# sondeSide.net
KiCad netlist of a schematic drawn in EAGLE
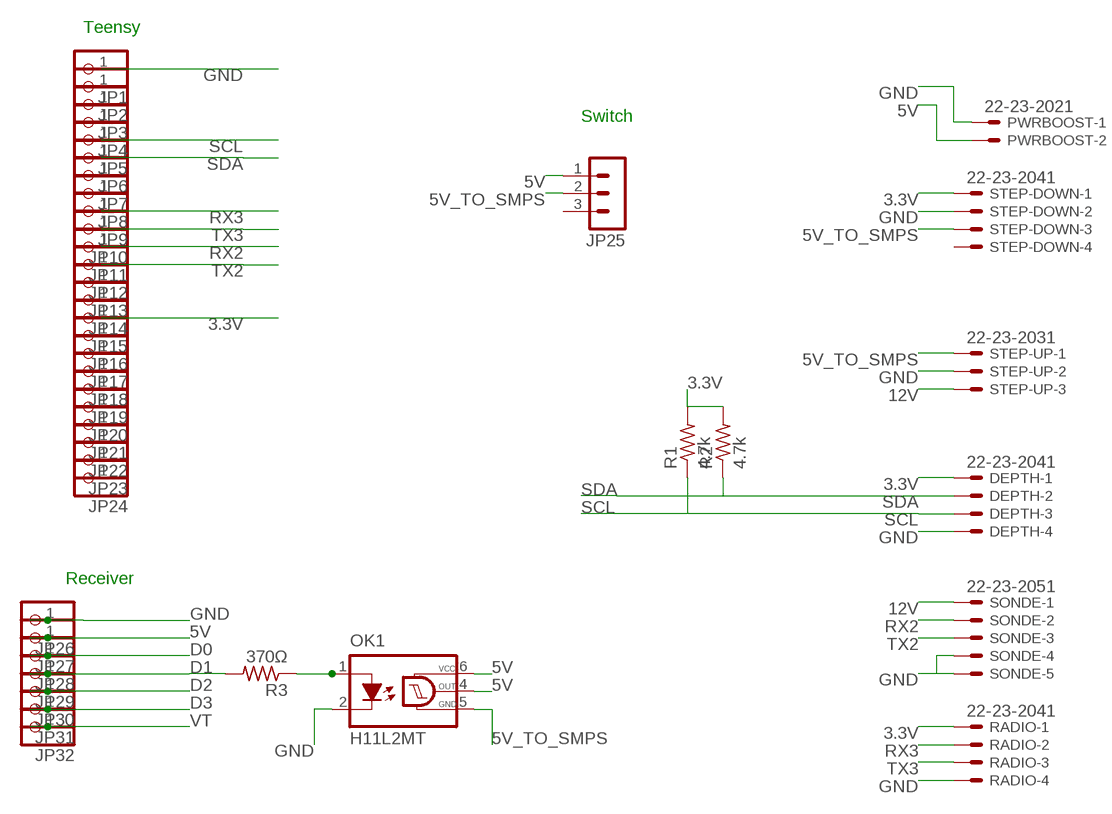
[diagram p0: schematic, sheet 1]

(export (version "E")
  (design (tool "Eeschema 10.0.6"))
  (components
    (comp (ref "DEPTH")
      (value "22-23-2041")
      (footprint "eagle-import:22-23-2041")
      (fields (field (name "MF") "MOLEX"))
      (libsource (lib "eagle-import") (part "22-23-2041"))
    )
    (comp (ref "JP1")
      (value "PINHD-1X1")
      (footprint "eagle-import:1X01")
      (libsource (lib "eagle-import") (part "PINHD-1X1"))
    )
    (comp (ref "JP2")
      (value "PINHD-1X1")
      (footprint "eagle-import:1X01")
      (libsource (lib "eagle-import") (part "PINHD-1X1"))
    )
    (comp (ref "JP3")
      (value "PINHD-1X1")
      (footprint "eagle-import:1X01")
      (libsource (lib "eagle-import") (part "PINHD-1X1"))
    )
    (comp (ref "JP4")
      (value "PINHD-1X1")
      (footprint "eagle-import:1X01")
      (libsource (lib "eagle-import") (part "PINHD-1X1"))
    )
    (comp (ref "JP5")
      (value "PINHD-1X1")
      (footprint "eagle-import:1X01")
      (libsource (lib "eagle-import") (part "PINHD-1X1"))
    )
    (comp (ref "JP6")
      (value "PINHD-1X1")
      (footprint "eagle-import:1X01")
      (libsource (lib "eagle-import") (part "PINHD-1X1"))
    )
    (comp (ref "JP7")
      (value "PINHD-1X1")
      (footprint "eagle-import:1X01")
      (libsource (lib "eagle-import") (part "PINHD-1X1"))
    )
    (comp (ref "JP8")
      (value "PINHD-1X1")
      (footprint "eagle-import:1X01")
      (libsource (lib "eagle-import") (part "PINHD-1X1"))
    )
    (comp (ref "JP9")
      (value "PINHD-1X1")
      (footprint "eagle-import:1X01")
      (libsource (lib "eagle-import") (part "PINHD-1X1"))
    )
    (comp (ref "JP10")
      (value "PINHD-1X1")
      (footprint "eagle-import:1X01")
      (libsource (lib "eagle-import") (part "PINHD-1X1"))
    )
    (comp (ref "JP11")
      (value "PINHD-1X1")
      (footprint "eagle-import:1X01")
      (libsource (lib "eagle-import") (part "PINHD-1X1"))
    )
    (comp (ref "JP12")
      (value "PINHD-1X1")
      (footprint "eagle-import:1X01")
      (libsource (lib "eagle-import") (part "PINHD-1X1"))
    )
    (comp (ref "JP13")
      (value "PINHD-1X1")
      (footprint "eagle-import:1X01")
      (libsource (lib "eagle-import") (part "PINHD-1X1"))
    )
    (comp (ref "JP14")
      (value "PINHD-1X1")
      (footprint "eagle-import:1X01")
      (libsource (lib "eagle-import") (part "PINHD-1X1"))
    )
    (comp (ref "JP15")
      (value "PINHD-1X1")
      (footprint "eagle-import:1X01")
      (libsource (lib "eagle-import") (part "PINHD-1X1"))
    )
    (comp (ref "JP16")
      (value "PINHD-1X1")
      (footprint "eagle-import:1X01")
      (libsource (lib "eagle-import") (part "PINHD-1X1"))
    )
    (comp (ref "JP17")
      (value "PINHD-1X1")
      (footprint "eagle-import:1X01")
      (libsource (lib "eagle-import") (part "PINHD-1X1"))
    )
    (comp (ref "JP18")
      (value "PINHD-1X1")
      (footprint "eagle-import:1X01")
      (libsource (lib "eagle-import") (part "PINHD-1X1"))
    )
    (comp (ref "JP19")
      (value "PINHD-1X1")
      (footprint "eagle-import:1X01")
      (libsource (lib "eagle-import") (part "PINHD-1X1"))
    )
    (comp (ref "JP20")
      (value "PINHD-1X1")
      (footprint "eagle-import:1X01")
      (libsource (lib "eagle-import") (part "PINHD-1X1"))
    )
    (comp (ref "JP21")
      (value "PINHD-1X1")
      (footprint "eagle-import:1X01")
      (libsource (lib "eagle-import") (part "PINHD-1X1"))
    )
    (comp (ref "JP22")
      (value "PINHD-1X1")
      (footprint "eagle-import:1X01")
      (libsource (lib "eagle-import") (part "PINHD-1X1"))
    )
    (comp (ref "JP23")
      (value "PINHD-1X1")
      (footprint "eagle-import:1X01")
      (libsource (lib "eagle-import") (part "PINHD-1X1"))
    )
    (comp (ref "JP24")
      (value "PINHD-1X1")
      (footprint "eagle-import:1X01")
      (libsource (lib "eagle-import") (part "PINHD-1X1"))
    )
    (comp (ref "JP25")
      (value "MA03-1")
      (footprint "eagle-import:MA03-1")
      (libsource (lib "eagle-import") (part "MA03-1"))
    )
    (comp (ref "JP26")
      (value "PINHD-1X1")
      (footprint "eagle-import:1X01")
      (libsource (lib "eagle-import") (part "PINHD-1X1"))
    )
    (comp (ref "JP27")
      (value "PINHD-1X1")
      (footprint "eagle-import:1X01")
      (libsource (lib "eagle-import") (part "PINHD-1X1"))
    )
    (comp (ref "JP28")
      (value "PINHD-1X1")
      (footprint "eagle-import:1X01")
      (libsource (lib "eagle-import") (part "PINHD-1X1"))
    )
    (comp (ref "JP29")
      (value "PINHD-1X1")
      (footprint "eagle-import:1X01")
      (libsource (lib "eagle-import") (part "PINHD-1X1"))
    )
    (comp (ref "JP30")
      (value "PINHD-1X1")
      (footprint "eagle-import:1X01")
      (libsource (lib "eagle-import") (part "PINHD-1X1"))
    )
    (comp (ref "JP31")
      (value "PINHD-1X1")
      (footprint "eagle-import:1X01")
      (libsource (lib "eagle-import") (part "PINHD-1X1"))
    )
    (comp (ref "JP32")
      (value "PINHD-1X1")
      (footprint "eagle-import:1X01")
      (libsource (lib "eagle-import") (part "PINHD-1X1"))
    )
    (comp (ref "OK1")
      (value "H11L2MT")
      (footprint "eagle-import:DIL6-04")
      (libsource (lib "eagle-import") (part "H11LMT2"))
    )
    (comp (ref "PWRBOOST")
      (value "22-23-2021")
      (footprint "eagle-import:22-23-2021")
      (fields (field (name "MF") "MOLEX"))
      (libsource (lib "eagle-import") (part "22-23-2021"))
    )
    (comp (ref "R1")
      (value "4.7k")
      (footprint "eagle-import:0204_7")
      (libsource (lib "eagle-import") (part "R-US_0204/7"))
    )
    (comp (ref "R2")
      (value "4.7k")
      (footprint "eagle-import:0204_7")
      (libsource (lib "eagle-import") (part "R-US_0204/7"))
    )
    (comp (ref "R3")
      (value "370Ω")
      (footprint "eagle-import:0204V")
      (libsource (lib "eagle-import") (part "R-US_0204/2V"))
    )
    (comp (ref "RADIO")
      (value "22-23-2041")
      (footprint "eagle-import:22-23-2041")
      (fields (field (name "MF") "MOLEX"))
      (libsource (lib "eagle-import") (part "22-23-2041"))
    )
    (comp (ref "SONDE")
      (value "22-23-2051")
      (footprint "eagle-import:22-23-2051")
      (fields (field (name "MF") "MOLEX"))
      (libsource (lib "eagle-import") (part "22-23-2051"))
    )
    (comp (ref "STEP-DOWN")
      (value "22-23-2041")
      (footprint "eagle-import:22-23-2041")
      (fields (field (name "MF") "MOLEX"))
      (libsource (lib "eagle-import") (part "22-23-2041"))
    )
    (comp (ref "STEP-UP")
      (value "22-23-2031")
      (footprint "eagle-import:22-23-2031")
      (fields (field (name "MF") "MOLEX"))
      (libsource (lib "eagle-import") (part "22-23-2031"))
    )
  )
  (nets
    (net (code "1") (name "/3.3V") (class "Default")
      (node (ref "DEPTH") (pin "1") (pinfunction "S_1") (pintype "passive"))
      (node (ref "JP15") (pin "1") (pinfunction "1_1") (pintype "passive"))
      (node (ref "R1") (pin "2") (pinfunction "2_2") (pintype "passive"))
      (node (ref "R2") (pin "2") (pinfunction "2_2") (pintype "passive"))
      (node (ref "RADIO") (pin "1") (pinfunction "S_1") (pintype "passive"))
      (node (ref "STEP-DOWN") (pin "1") (pinfunction "S_1") (pintype "passive"))
    )
    (net (code "2") (name "/5V") (class "Default")
      (node (ref "JP25") (pin "1") (pinfunction "1_1") (pintype "passive"))
      (node (ref "JP27") (pin "1") (pinfunction "1_1") (pintype "passive"))
      (node (ref "OK1") (pin "4") (pinfunction "OUT_4") (pintype "output"))
      (node (ref "OK1") (pin "6") (pinfunction "VCC_6") (pintype "power_in"))
      (node (ref "PWRBOOST") (pin "2") (pinfunction "S_2") (pintype "passive"))
    )
    (net (code "3") (name "/5V_TO_SMPS") (class "Default")
      (node (ref "JP25") (pin "2") (pinfunction "2_2") (pintype "passive"))
      (node (ref "OK1") (pin "5") (pinfunction "GND_5") (pintype "power_in"))
      (node (ref "STEP-DOWN") (pin "3") (pinfunction "S_3") (pintype "passive"))
      (node (ref "STEP-UP") (pin "1") (pinfunction "S_1") (pintype "passive"))
    )
    (net (code "4") (name "/12V") (class "Default")
      (node (ref "SONDE") (pin "1") (pinfunction "S_1") (pintype "passive"))
      (node (ref "STEP-UP") (pin "3") (pinfunction "S_3") (pintype "passive"))
    )
    (net (code "5") (name "/D0") (class "Default")
      (node (ref "JP28") (pin "1") (pinfunction "1_1") (pintype "passive"))
    )
    (net (code "6") (name "/D1") (class "Default")
      (node (ref "JP29") (pin "1") (pinfunction "1_1") (pintype "passive"))
      (node (ref "R3") (pin "2") (pinfunction "2_2") (pintype "passive"))
    )
    (net (code "7") (name "/D2") (class "Default")
      (node (ref "JP30") (pin "1") (pinfunction "1_1") (pintype "passive"))
    )
    (net (code "8") (name "/D3") (class "Default")
      (node (ref "JP31") (pin "1") (pinfunction "1_1") (pintype "passive"))
    )
    (net (code "9") (name "/GND") (class "Default")
      (node (ref "DEPTH") (pin "4") (pinfunction "S_4") (pintype "passive"))
      (node (ref "JP1") (pin "1") (pinfunction "1_1") (pintype "passive"))
      (node (ref "JP26") (pin "1") (pinfunction "1_1") (pintype "passive"))
      (node (ref "OK1") (pin "2") (pinfunction "C_2") (pintype "passive"))
      (node (ref "PWRBOOST") (pin "1") (pinfunction "S_1") (pintype "passive"))
      (node (ref "RADIO") (pin "4") (pinfunction "S_4") (pintype "passive"))
      (node (ref "SONDE") (pin "4") (pinfunction "S_4") (pintype "passive"))
      (node (ref "SONDE") (pin "5") (pinfunction "S_5") (pintype "passive"))
      (node (ref "STEP-DOWN") (pin "2") (pinfunction "S_2") (pintype "passive"))
      (node (ref "STEP-UP") (pin "2") (pinfunction "S_2") (pintype "passive"))
    )
    (net (code "10") (name "/RX2") (class "Default")
      (node (ref "JP11") (pin "1") (pinfunction "1_1") (pintype "passive"))
      (node (ref "SONDE") (pin "2") (pinfunction "S_2") (pintype "passive"))
    )
    (net (code "11") (name "/RX3") (class "Default")
      (node (ref "JP9") (pin "1") (pinfunction "1_1") (pintype "passive"))
      (node (ref "RADIO") (pin "2") (pinfunction "S_2") (pintype "passive"))
    )
    (net (code "12") (name "/SCL") (class "Default")
      (node (ref "DEPTH") (pin "3") (pinfunction "S_3") (pintype "passive"))
      (node (ref "JP5") (pin "1") (pinfunction "1_1") (pintype "passive"))
      (node (ref "R1") (pin "1") (pinfunction "1_1") (pintype "passive"))
    )
    (net (code "13") (name "/SDA") (class "Default")
      (node (ref "DEPTH") (pin "2") (pinfunction "S_2") (pintype "passive"))
      (node (ref "JP6") (pin "1") (pinfunction "1_1") (pintype "passive"))
      (node (ref "R2") (pin "1") (pinfunction "1_1") (pintype "passive"))
    )
    (net (code "14") (name "/TX2") (class "Default")
      (node (ref "JP12") (pin "1") (pinfunction "1_1") (pintype "passive"))
      (node (ref "SONDE") (pin "3") (pinfunction "S_3") (pintype "passive"))
    )
    (net (code "15") (name "/TX3") (class "Default")
      (node (ref "JP10") (pin "1") (pinfunction "1_1") (pintype "passive"))
      (node (ref "RADIO") (pin "3") (pinfunction "S_3") (pintype "passive"))
    )
    (net (code "16") (name "/VT") (class "Default")
      (node (ref "JP32") (pin "1") (pinfunction "1_1") (pintype "passive"))
    )
    (net (code "17") (name "Net-(OK1-A)") (class "Default")
      (node (ref "OK1") (pin "1") (pinfunction "A_1") (pintype "passive"))
      (node (ref "R3") (pin "1") (pinfunction "1_1") (pintype "passive"))
    )
    (net (code "18") (name "unconnected-(JP2-Pad1)") (class "Default")
      (node (ref "JP2") (pin "1") (pinfunction "1_1") (pintype "passive"))
    )
    (net (code "19") (name "unconnected-(JP3-Pad1)") (class "Default")
      (node (ref "JP3") (pin "1") (pinfunction "1_1") (pintype "passive"))
    )
    (net (code "20") (name "unconnected-(JP4-Pad1)") (class "Default")
      (node (ref "JP4") (pin "1") (pinfunction "1_1") (pintype "passive"))
    )
    (net (code "21") (name "unconnected-(JP7-Pad1)") (class "Default")
      (node (ref "JP7") (pin "1") (pinfunction "1_1") (pintype "passive"))
    )
    (net (code "22") (name "unconnected-(JP8-Pad1)") (class "Default")
      (node (ref "JP8") (pin "1") (pinfunction "1_1") (pintype "passive"))
    )
    (net (code "23") (name "unconnected-(JP13-Pad1)") (class "Default")
      (node (ref "JP13") (pin "1") (pinfunction "1_1") (pintype "passive"))
    )
    (net (code "24") (name "unconnected-(JP14-Pad1)") (class "Default")
      (node (ref "JP14") (pin "1") (pinfunction "1_1") (pintype "passive"))
    )
    (net (code "25") (name "unconnected-(JP16-Pad1)") (class "Default")
      (node (ref "JP16") (pin "1") (pinfunction "1_1") (pintype "passive"))
    )
    (net (code "26") (name "unconnected-(JP17-Pad1)") (class "Default")
      (node (ref "JP17") (pin "1") (pinfunction "1_1") (pintype "passive"))
    )
    (net (code "27") (name "unconnected-(JP18-Pad1)") (class "Default")
      (node (ref "JP18") (pin "1") (pinfunction "1_1") (pintype "passive"))
    )
    (net (code "28") (name "unconnected-(JP19-Pad1)") (class "Default")
      (node (ref "JP19") (pin "1") (pinfunction "1_1") (pintype "passive"))
    )
    (net (code "29") (name "unconnected-(JP20-Pad1)") (class "Default")
      (node (ref "JP20") (pin "1") (pinfunction "1_1") (pintype "passive"))
    )
    (net (code "30") (name "unconnected-(JP21-Pad1)") (class "Default")
      (node (ref "JP21") (pin "1") (pinfunction "1_1") (pintype "passive"))
    )
    (net (code "31") (name "unconnected-(JP22-Pad1)") (class "Default")
      (node (ref "JP22") (pin "1") (pinfunction "1_1") (pintype "passive"))
    )
    (net (code "32") (name "unconnected-(JP23-Pad1)") (class "Default")
      (node (ref "JP23") (pin "1") (pinfunction "1_1") (pintype "passive"))
    )
    (net (code "33") (name "unconnected-(JP24-Pad1)") (class "Default")
      (node (ref "JP24") (pin "1") (pinfunction "1_1") (pintype "passive"))
    )
    (net (code "34") (name "unconnected-(JP25-Pad3)") (class "Default")
      (node (ref "JP25") (pin "3") (pinfunction "3_3") (pintype "passive"))
    )
    (net (code "35") (name "unconnected-(STEP-DOWND-S-Pad4)") (class "Default")
      (node (ref "STEP-DOWN") (pin "4") (pinfunction "S_4") (pintype "passive"))
    )
  )
)
